# flash.net
KiCad netlist of a schematic drawn in Altium Designer
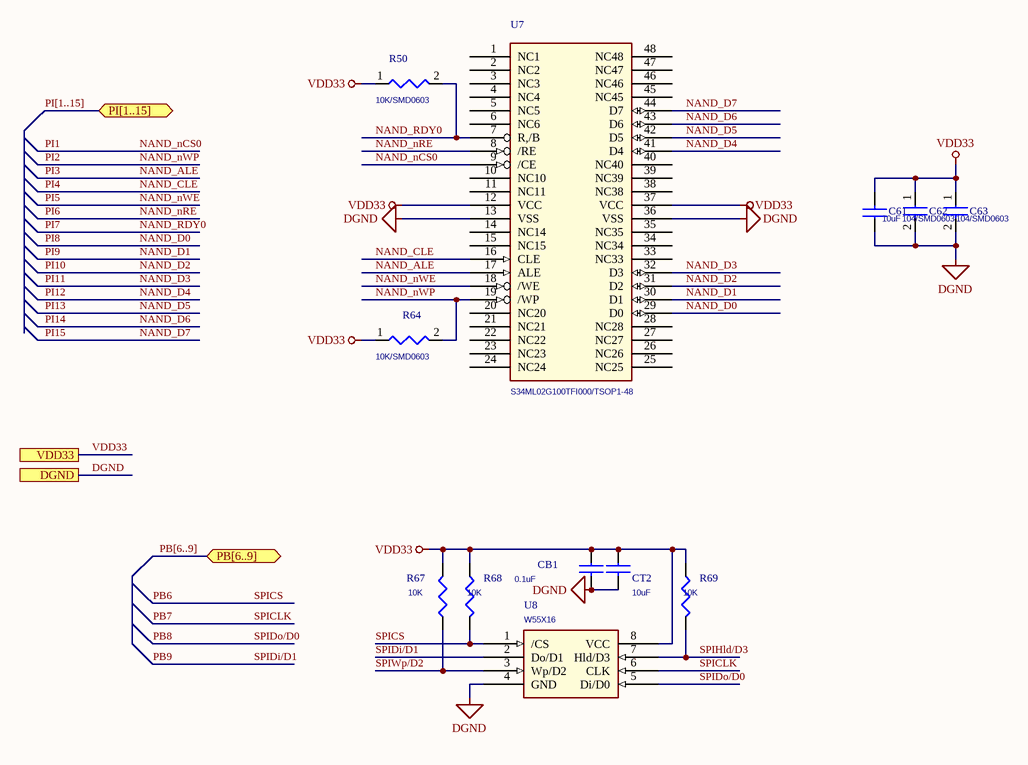
[diagram p0: flash.SchDoc]

(export (version "E")
  (design (tool "Eeschema 10.0.6"))
  (components
    (comp (ref "C61") (value "10uF") (footprint "C0805") (libsource (lib "*") (part "CAP NP_Dup1")))
    (comp (ref "C62") (value "104/SMD0603") (footprint "0603C") (libsource (lib "*") (part "C/SMD0603")))
    (comp (ref "C63") (value "104/SMD0603") (footprint "0603C") (libsource (lib "*") (part "C/SMD0603")))
    (comp (ref "CB1") (value "0.1uF") (footprint "0603C") (libsource (lib "*") (part "CAP NP_Dup1")))
    (comp (ref "CT2") (value "10uF") (footprint "C0805") (libsource (lib "*") (part "CAP NP_Dup1")))
    (comp (ref "R50") (value "10K/SMD0603") (footprint "0603R") (libsource (lib "*") (part "R/SMD0603")))
    (comp (ref "R64") (value "10K/SMD0603") (footprint "0603R") (libsource (lib "*") (part "R/SMD0603")))
    (comp (ref "R67") (value "10K") (footprint "0603R") (libsource (lib "*") (part "R_Dup1")))
    (comp (ref "R68") (value "10K") (footprint "0603R") (libsource (lib "*") (part "R_Dup1")))
    (comp (ref "R69") (value "10K") (footprint "0603R") (libsource (lib "*") (part "R_Dup1")))
    (comp (ref "U7")
      (value "S34ML02G100TFI000/TSOP1-48")
      (footprint "TSOP48-0.5MM")
      (libsource (lib "*") (part "S34ML02G100TFI000/TSOP1-48"))
    )
    (comp (ref "U8") (value "W55X16") (footprint "VDFPN8") (libsource (lib "*") (part "W55X10_2")))
  )
  (nets
    (net (code "1") (name "/PB6") (class "Default")
      (node (ref "R68") (pin "1") (pinfunction "1_1") (pintype "passive"))
      (node (ref "U8") (pin "1") (pinfunction "/CS_1") (pintype "input"))
    )
    (net (code "2") (name "/PB7") (class "Default")
      (node (ref "U8") (pin "6") (pinfunction "CLK_6") (pintype "input"))
    )
    (net (code "3") (name "/PB8") (class "Default")
      (node (ref "U8") (pin "5") (pinfunction "Di/D0_5") (pintype "input"))
    )
    (net (code "4") (name "/PB9") (class "Default")
      (node (ref "U8") (pin "2") (pinfunction "Do/D1_2") (pintype "passive"))
    )
    (net (code "6") (name "/PI1") (class "Default")
      (node (ref "U7") (pin "9") (pinfunction "/CE_9") (pintype "input"))
    )
    (net (code "7") (name "/PI2") (class "Default")
      (node (ref "R64") (pin "2") (pinfunction "2_2") (pintype "passive"))
      (node (ref "U7") (pin "19") (pinfunction "/WP_19") (pintype "input"))
    )
    (net (code "8") (name "/PI3") (class "Default")
      (node (ref "U7") (pin "17") (pinfunction "ALE_17") (pintype "input"))
    )
    (net (code "9") (name "/PI4") (class "Default")
      (node (ref "U7") (pin "16") (pinfunction "CLE_16") (pintype "input"))
    )
    (net (code "10") (name "/PI5") (class "Default")
      (node (ref "U7") (pin "18") (pinfunction "/WE_18") (pintype "input"))
    )
    (net (code "11") (name "/PI6") (class "Default")
      (node (ref "U7") (pin "8") (pinfunction "/RE_8") (pintype "input"))
    )
    (net (code "12") (name "/PI7") (class "Default")
      (node (ref "R50") (pin "2") (pinfunction "2_2") (pintype "passive"))
      (node (ref "U7") (pin "7") (pinfunction "R,/B_7") (pintype "open_collector"))
    )
    (net (code "13") (name "/PI8") (class "Default")
      (node (ref "U7") (pin "29") (pinfunction "D0_29") (pintype "bidirectional"))
    )
    (net (code "14") (name "/PI9") (class "Default")
      (node (ref "U7") (pin "30") (pinfunction "D1_30") (pintype "bidirectional"))
    )
    (net (code "15") (name "/PI10") (class "Default")
      (node (ref "U7") (pin "31") (pinfunction "D2_31") (pintype "bidirectional"))
    )
    (net (code "16") (name "/PI11") (class "Default")
      (node (ref "U7") (pin "32") (pinfunction "D3_32") (pintype "bidirectional"))
    )
    (net (code "17") (name "/PI12") (class "Default")
      (node (ref "U7") (pin "41") (pinfunction "D4_41") (pintype "bidirectional"))
    )
    (net (code "18") (name "/PI13") (class "Default")
      (node (ref "U7") (pin "42") (pinfunction "D5_42") (pintype "bidirectional"))
    )
    (net (code "19") (name "/PI14") (class "Default")
      (node (ref "U7") (pin "43") (pinfunction "D6_43") (pintype "bidirectional"))
    )
    (net (code "20") (name "/PI15") (class "Default")
      (node (ref "U7") (pin "44") (pinfunction "D7_44") (pintype "bidirectional"))
    )
    (net (code "22") (name "/SPIHld{slash}D3") (class "Default")
      (node (ref "R69") (pin "1") (pinfunction "1_1") (pintype "passive"))
      (node (ref "U8") (pin "7") (pinfunction "Hld/D3_7") (pintype "input"))
    )
    (net (code "23") (name "/SPIWp{slash}D2") (class "Default")
      (node (ref "R67") (pin "1") (pinfunction "1_1") (pintype "passive"))
      (node (ref "U8") (pin "3") (pinfunction "Wp/D2_3") (pintype "input"))
    )
    (net (code "24") (name "DGND") (class "Default")
      (node (ref "C61") (pin "1") (pinfunction "1_1") (pintype "passive"))
      (node (ref "C62") (pin "2") (pinfunction "2_2") (pintype "passive"))
      (node (ref "C63") (pin "2") (pinfunction "2_2") (pintype "passive"))
      (node (ref "CB1") (pin "2") (pinfunction "2_2") (pintype "passive"))
      (node (ref "CT2") (pin "2") (pinfunction "2_2") (pintype "passive"))
      (node (ref "U7") (pin "13") (pinfunction "VSS_13") (pintype "power_in"))
      (node (ref "U7") (pin "36") (pinfunction "VSS_36") (pintype "power_in"))
      (node (ref "U8") (pin "4") (pinfunction "GND_4") (pintype "power_in"))
    )
    (net (code "25") (name "VDD33") (class "Default")
      (node (ref "C61") (pin "2") (pinfunction "2_2") (pintype "passive"))
      (node (ref "C62") (pin "1") (pinfunction "1_1") (pintype "passive"))
      (node (ref "C63") (pin "1") (pinfunction "1_1") (pintype "passive"))
      (node (ref "CB1") (pin "1") (pinfunction "1_1") (pintype "passive"))
      (node (ref "CT2") (pin "1") (pinfunction "1_1") (pintype "passive"))
      (node (ref "R50") (pin "1") (pinfunction "1_1") (pintype "passive"))
      (node (ref "R64") (pin "1") (pinfunction "1_1") (pintype "passive"))
      (node (ref "R67") (pin "2") (pinfunction "2_2") (pintype "passive"))
      (node (ref "R68") (pin "2") (pinfunction "2_2") (pintype "passive"))
      (node (ref "R69") (pin "2") (pinfunction "2_2") (pintype "passive"))
      (node (ref "U7") (pin "12") (pinfunction "VCC_12") (pintype "power_in"))
      (node (ref "U7") (pin "37") (pinfunction "VCC_37") (pintype "power_in"))
      (node (ref "U8") (pin "8") (pinfunction "VCC_8") (pintype "power_in"))
    )
    (net (code "26") (name "unconnected-(U7-NC1-Pad1)") (class "Default")
      (node (ref "U7") (pin "1") (pinfunction "NC1_1") (pintype "passive"))
    )
    (net (code "27") (name "unconnected-(U7-NC2-Pad2)") (class "Default")
      (node (ref "U7") (pin "2") (pinfunction "NC2_2") (pintype "passive"))
    )
    (net (code "28") (name "unconnected-(U7-NC3-Pad3)") (class "Default")
      (node (ref "U7") (pin "3") (pinfunction "NC3_3") (pintype "passive"))
    )
    (net (code "29") (name "unconnected-(U7-NC4-Pad4)") (class "Default")
      (node (ref "U7") (pin "4") (pinfunction "NC4_4") (pintype "passive"))
    )
    (net (code "30") (name "unconnected-(U7-NC5-Pad5)") (class "Default")
      (node (ref "U7") (pin "5") (pinfunction "NC5_5") (pintype "passive"))
    )
    (net (code "31") (name "unconnected-(U7-NC6-Pad6)") (class "Default")
      (node (ref "U7") (pin "6") (pinfunction "NC6_6") (pintype "passive"))
    )
    (net (code "32") (name "unconnected-(U7-NC10-Pad10)") (class "Default")
      (node (ref "U7") (pin "10") (pinfunction "NC10_10") (pintype "passive"))
    )
    (net (code "33") (name "unconnected-(U7-NC11-Pad11)") (class "Default")
      (node (ref "U7") (pin "11") (pinfunction "NC11_11") (pintype "passive"))
    )
    (net (code "34") (name "unconnected-(U7-NC14-Pad14)") (class "Default")
      (node (ref "U7") (pin "14") (pinfunction "NC14_14") (pintype "passive"))
    )
    (net (code "35") (name "unconnected-(U7-NC15-Pad15)") (class "Default")
      (node (ref "U7") (pin "15") (pinfunction "NC15_15") (pintype "passive"))
    )
    (net (code "36") (name "unconnected-(U7-NC20-Pad20)") (class "Default")
      (node (ref "U7") (pin "20") (pinfunction "NC20_20") (pintype "passive"))
    )
    (net (code "37") (name "unconnected-(U7-NC21-Pad21)") (class "Default")
      (node (ref "U7") (pin "21") (pinfunction "NC21_21") (pintype "passive"))
    )
    (net (code "38") (name "unconnected-(U7-NC22-Pad22)") (class "Default")
      (node (ref "U7") (pin "22") (pinfunction "NC22_22") (pintype "passive"))
    )
    (net (code "39") (name "unconnected-(U7-NC23-Pad23)") (class "Default")
      (node (ref "U7") (pin "23") (pinfunction "NC23_23") (pintype "passive"))
    )
    (net (code "40") (name "unconnected-(U7-NC24-Pad24)") (class "Default")
      (node (ref "U7") (pin "24") (pinfunction "NC24_24") (pintype "passive"))
    )
    (net (code "41") (name "unconnected-(U7-NC25-Pad25)") (class "Default")
      (node (ref "U7") (pin "25") (pinfunction "NC25_25") (pintype "passive"))
    )
    (net (code "42") (name "unconnected-(U7-NC26-Pad26)") (class "Default")
      (node (ref "U7") (pin "26") (pinfunction "NC26_26") (pintype "passive"))
    )
    (net (code "43") (name "unconnected-(U7-NC27-Pad27)") (class "Default")
      (node (ref "U7") (pin "27") (pinfunction "NC27_27") (pintype "passive"))
    )
    (net (code "44") (name "unconnected-(U7-NC28-Pad28)") (class "Default")
      (node (ref "U7") (pin "28") (pinfunction "NC28_28") (pintype "passive"))
    )
    (net (code "45") (name "unconnected-(U7-NC33-Pad33)") (class "Default")
      (node (ref "U7") (pin "33") (pinfunction "NC33_33") (pintype "passive"))
    )
    (net (code "46") (name "unconnected-(U7-NC34-Pad34)") (class "Default")
      (node (ref "U7") (pin "34") (pinfunction "NC34_34") (pintype "passive"))
    )
    (net (code "47") (name "unconnected-(U7-NC35-Pad35)") (class "Default")
      (node (ref "U7") (pin "35") (pinfunction "NC35_35") (pintype "passive"))
    )
    (net (code "48") (name "unconnected-(U7-NC38-Pad38)") (class "Default")
      (node (ref "U7") (pin "38") (pinfunction "NC38_38") (pintype "passive"))
    )
    (net (code "49") (name "unconnected-(U7-NC39-Pad39)") (class "Default")
      (node (ref "U7") (pin "39") (pinfunction "NC39_39") (pintype "passive"))
    )
    (net (code "50") (name "unconnected-(U7-NC40-Pad40)") (class "Default")
      (node (ref "U7") (pin "40") (pinfunction "NC40_40") (pintype "passive"))
    )
    (net (code "51") (name "unconnected-(U7-NC45-Pad45)") (class "Default")
      (node (ref "U7") (pin "45") (pinfunction "NC45_45") (pintype "passive"))
    )
    (net (code "52") (name "unconnected-(U7-NC46-Pad46)") (class "Default")
      (node (ref "U7") (pin "46") (pinfunction "NC46_46") (pintype "passive"))
    )
    (net (code "53") (name "unconnected-(U7-NC47-Pad47)") (class "Default")
      (node (ref "U7") (pin "47") (pinfunction "NC47_47") (pintype "passive"))
    )
    (net (code "54") (name "unconnected-(U7-NC48-Pad48)") (class "Default")
      (node (ref "U7") (pin "48") (pinfunction "NC48_48") (pintype "passive"))
    )
  )
)
